# ProPrj.net
KiCad netlist of a schematic drawn in EasyEDA Pro
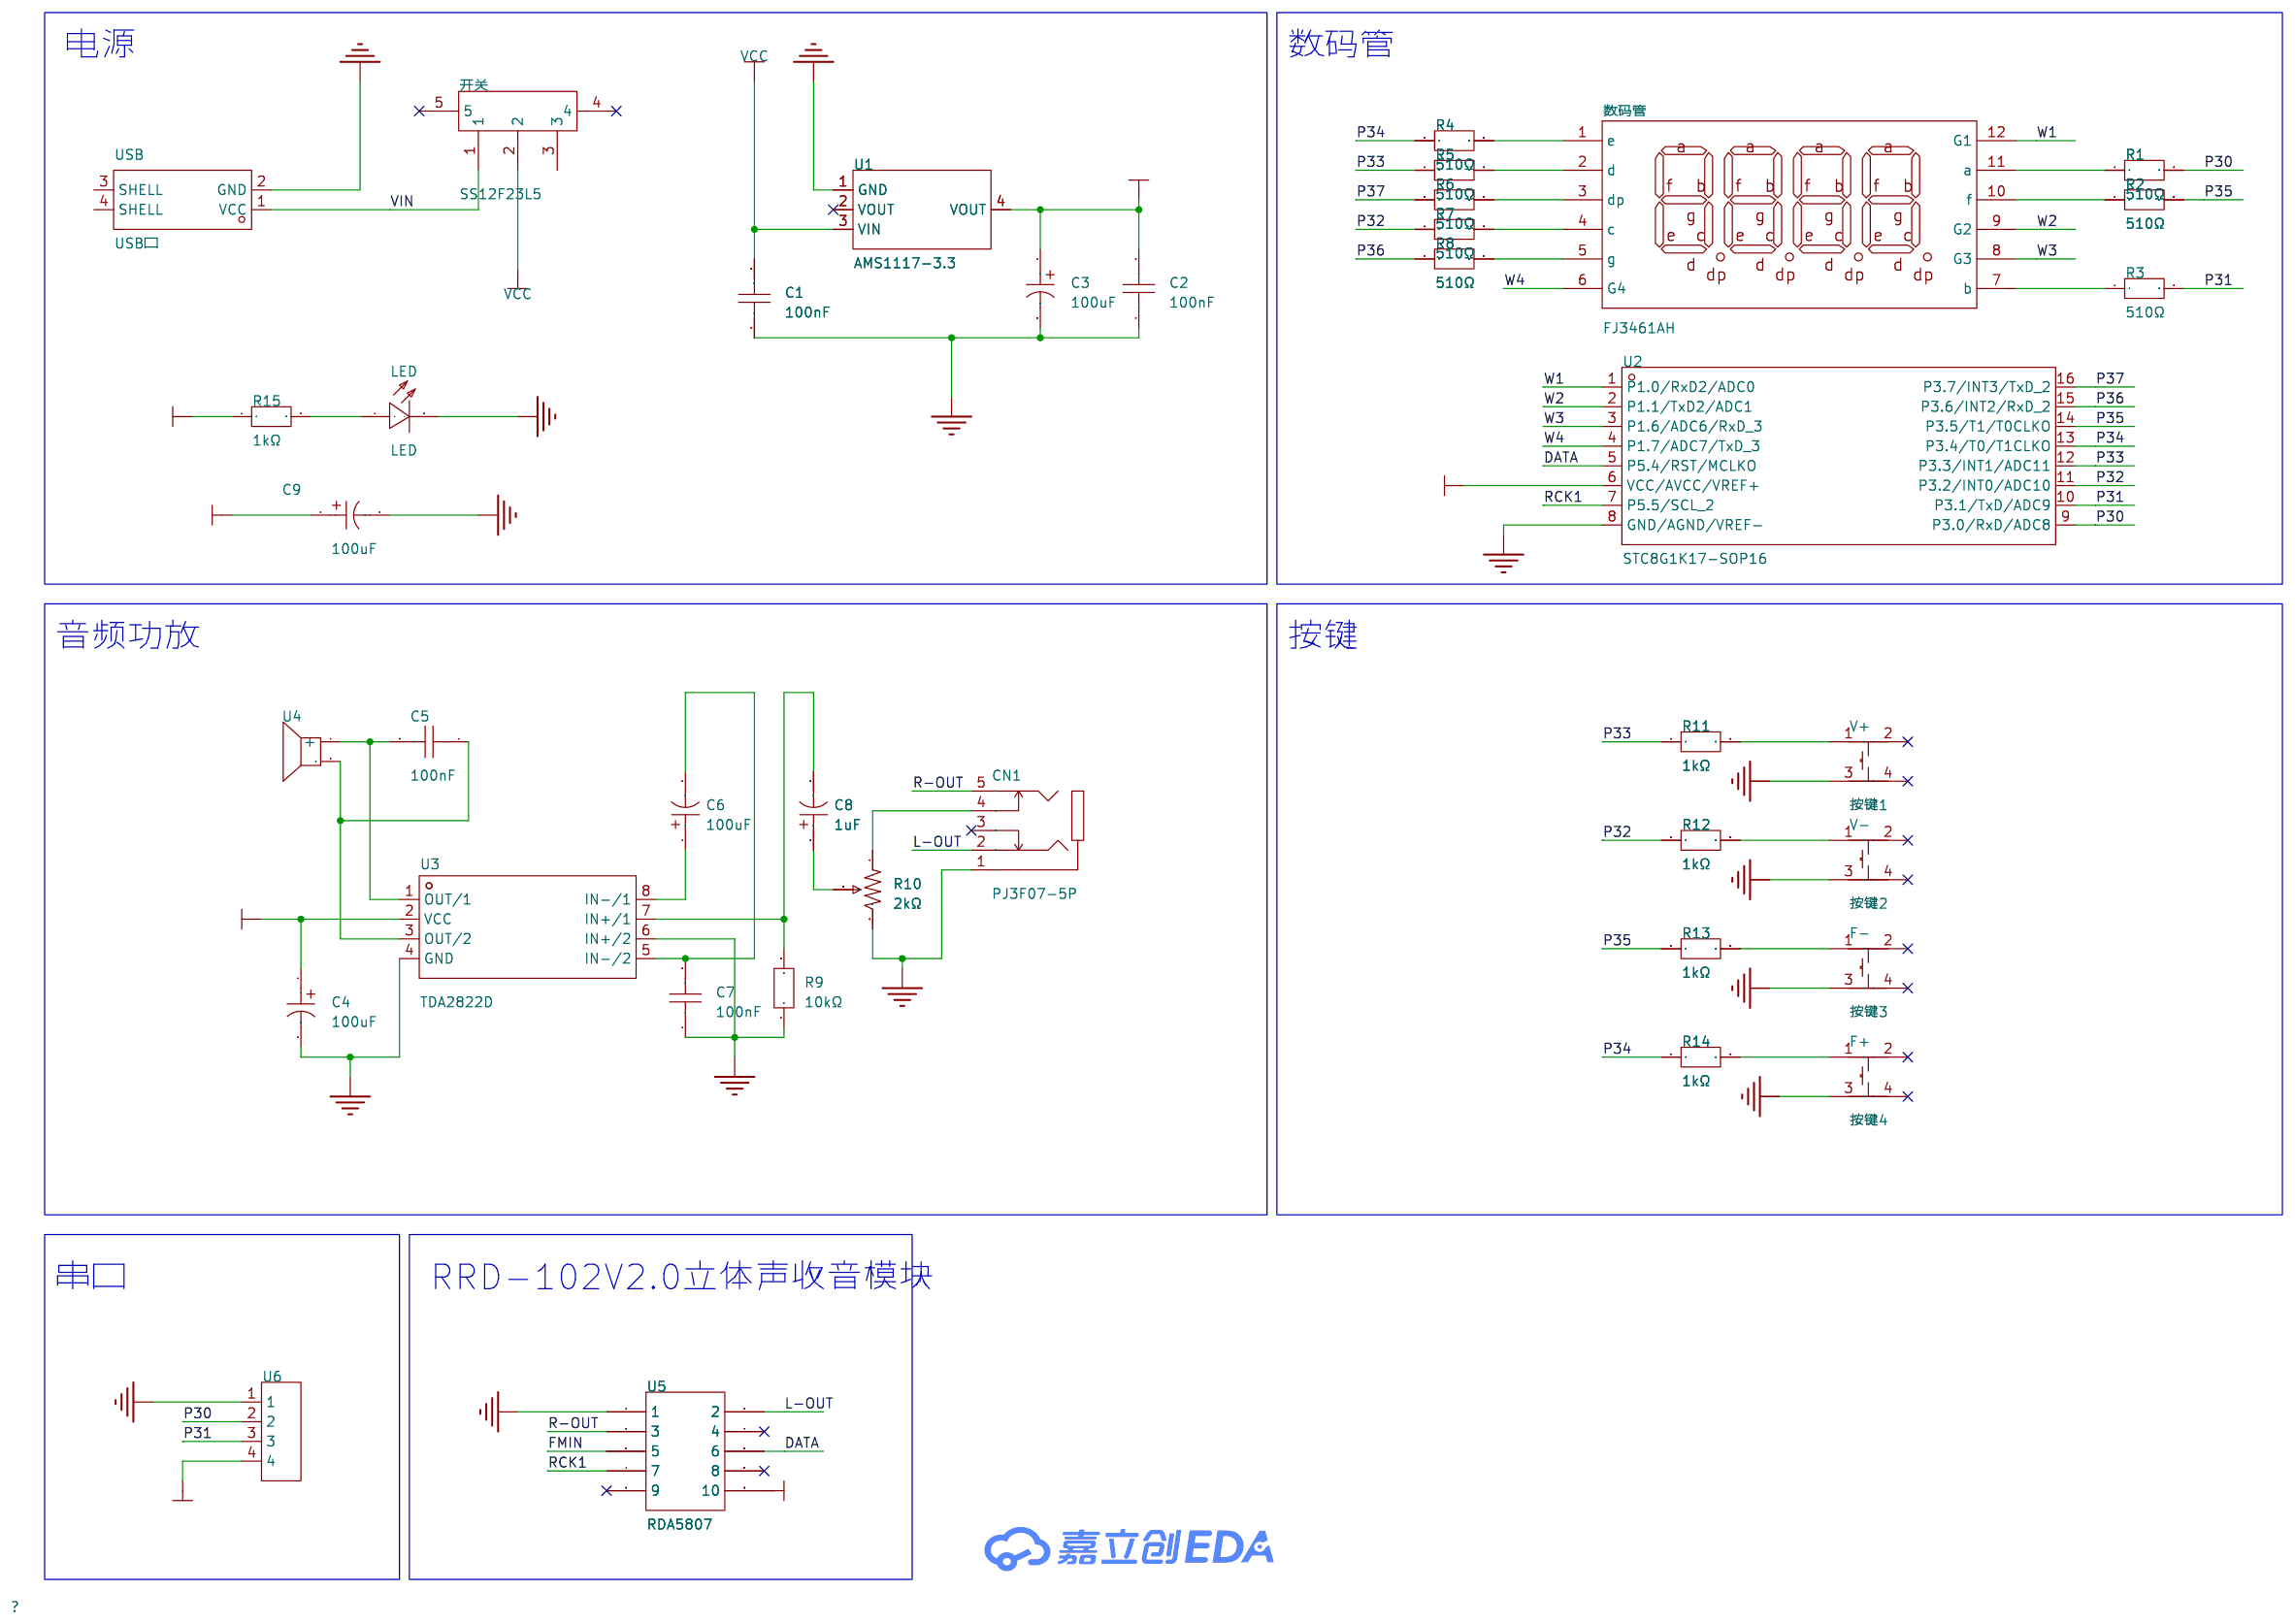
[diagram p0: P1]
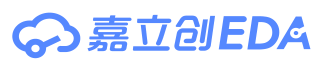
[diagram p1: P2]

(export (version "E")
  (design (tool "Eeschema 10.0.6"))
  (components
    (comp (ref "C1")
      (value "100nF")
      (footprint "easyedapro:C0603")
      (description "容值:100nF;精度:±10%;额定电压:50V;温度系数:X7R;")
      (fields
        (field (name "Manufacturer Part") "CC0603KRX7R9BB104")
        (field (name "Manufacturer") "YAGEO(国巨)")
      )
      (libsource (lib "easyedapro") (part "CC0603KRX7R9BB104"))
    )
    (comp (ref "C2")
      (value "100nF")
      (footprint "easyedapro:C0603")
      (description "容值:100nF;精度:±10%;额定电压:50V;温度系数:X7R;")
      (fields
        (field (name "Manufacturer Part") "CC0603KRX7R9BB104")
        (field (name "Manufacturer") "YAGEO(国巨)")
      )
      (libsource (lib "easyedapro") (part "CC0603KRX7R9BB104"))
    )
    (comp (ref "C3")
      (value "100uF")
      (footprint "easyedapro:CAP-TH_BD8.0-P3.50-D0.6-FD_1")
      (libsource (lib "easyedapro") (part "100UF_C9900016884"))
    )
    (comp (ref "C4")
      (value "100uF")
      (footprint "easyedapro:CAP-TH_BD8.0-P3.50-D0.6-FD_1")
      (libsource (lib "easyedapro") (part "100UF_C9900016884"))
    )
    (comp (ref "C5")
      (value "100nF")
      (footprint "easyedapro:C0603")
      (description "容值:100nF;精度:±10%;额定电压:50V;温度系数:X7R;")
      (fields
        (field (name "Manufacturer Part") "CC0603KRX7R9BB104")
        (field (name "Manufacturer") "YAGEO(国巨)")
      )
      (libsource (lib "easyedapro") (part "CC0603KRX7R9BB104"))
    )
    (comp (ref "C6")
      (value "100uF")
      (footprint "easyedapro:CAP-TH_BD8.0-P3.50-D0.6-FD_1")
      (libsource (lib "easyedapro") (part "100UF_C9900016884"))
    )
    (comp (ref "C7")
      (value "100nF")
      (footprint "easyedapro:C0603")
      (description "容值:100nF;精度:±10%;额定电压:50V;温度系数:X7R;")
      (fields
        (field (name "Manufacturer Part") "CC0603KRX7R9BB104")
        (field (name "Manufacturer") "YAGEO(国巨)")
      )
      (libsource (lib "easyedapro") (part "CC0603KRX7R9BB104"))
    )
    (comp (ref "C8")
      (value "1uF")
      (footprint "easyedapro:CAP-TH_BD8.0-P3.50-D0.6-FD_1")
      (fields (field (name "Manufacturer Part") "RST50V1M4X5") (field (name "Manufacturer") "JIERR(捷而瑞)"))
      (libsource (lib "easyedapro") (part "100UF_C9900016884"))
    )
    (comp (ref "C9")
      (value "100uF")
      (footprint "easyedapro:CAP-TH_BD8.0-P3.50-D0.6-FD_1")
      (libsource (lib "easyedapro") (part "100UF_C9900016884"))
    )
    (comp (ref "CN1")
      (value "PJ3F07-5P")
      (footprint "easyedapro:AUDIO-TH_PJ3F07-5P")
      (description "连接器类型:3.5mm耳机座;额定电流:500mA;额定电压:30V;触头材质:铜;触头镀层:银;工作温度:-30°C~+70°C;")
      (fields (field (name "Manufacturer") "SHOU HAN(首韩)"))
      (libsource (lib "easyedapro") (part "PJ3F07-5P"))
    )
    (comp (ref "F+")
      (value "按键4")
      (footprint "easyedapro:KEY-SMD_4P-L6.0-W6.0-P4.50-LS8.6")
      (fields (field (name "Manufacturer") "Megastar(兆星)"))
      (libsource (lib "easyedapro") (part "ZX-QC66-7.5TP"))
    )
    (comp (ref "F-")
      (value "按键3")
      (footprint "easyedapro:KEY-SMD_4P-L6.0-W6.0-P4.50-LS8.6")
      (fields (field (name "Manufacturer") "Megastar(兆星)"))
      (libsource (lib "easyedapro") (part "ZX-QC66-7.5TP"))
    )
    (comp (ref "LED")
      (value "LED")
      (footprint "easyedapro:LED-TH_BD4.0-P2.54-FD_RED")
      (libsource (lib "easyedapro") (part "LED_C9900015665"))
    )
    (comp (ref "R1")
      (value "510Ω")
      (footprint "easyedapro:R0402")
      (description "电阻类型:厚膜电阻;阻值:510Ω;精度:±1%;功率:62.5mW;工作电压:50V;温度系数:±100ppm/°C;")
      (fields
        (field (name "Manufacturer Part") "0805W8F5100T5E")
        (field (name "Manufacturer") "UNI-ROYAL(厚声)")
      )
      (libsource (lib "easyedapro") (part "FRC0402F5100TS"))
    )
    (comp (ref "R2")
      (value "510Ω")
      (footprint "easyedapro:R0402")
      (description "电阻类型:厚膜电阻;阻值:510Ω;精度:±1%;功率:62.5mW;工作电压:50V;温度系数:±100ppm/°C;")
      (fields
        (field (name "Manufacturer Part") "0805W8F5100T5E")
        (field (name "Manufacturer") "UNI-ROYAL(厚声)")
      )
      (libsource (lib "easyedapro") (part "FRC0402F5100TS"))
    )
    (comp (ref "R3")
      (value "510Ω")
      (footprint "easyedapro:R0402")
      (description "电阻类型:厚膜电阻;阻值:510Ω;精度:±1%;功率:62.5mW;工作电压:50V;温度系数:±100ppm/°C;")
      (fields
        (field (name "Manufacturer Part") "0805W8F5100T5E")
        (field (name "Manufacturer") "UNI-ROYAL(厚声)")
      )
      (libsource (lib "easyedapro") (part "FRC0402F5100TS"))
    )
    (comp (ref "R4")
      (value "510Ω")
      (footprint "easyedapro:R0402")
      (description "电阻类型:厚膜电阻;阻值:510Ω;精度:±1%;功率:62.5mW;工作电压:50V;温度系数:±100ppm/°C;")
      (fields
        (field (name "Manufacturer Part") "0805W8F5100T5E")
        (field (name "Manufacturer") "UNI-ROYAL(厚声)")
      )
      (libsource (lib "easyedapro") (part "FRC0402F5100TS"))
    )
    (comp (ref "R5")
      (value "510Ω")
      (footprint "easyedapro:R0402")
      (description "电阻类型:厚膜电阻;阻值:510Ω;精度:±1%;功率:62.5mW;工作电压:50V;温度系数:±100ppm/°C;")
      (fields
        (field (name "Manufacturer Part") "0805W8F5100T5E")
        (field (name "Manufacturer") "UNI-ROYAL(厚声)")
      )
      (libsource (lib "easyedapro") (part "FRC0402F5100TS"))
    )
    (comp (ref "R6")
      (value "510Ω")
      (footprint "easyedapro:R0402")
      (description "电阻类型:厚膜电阻;阻值:510Ω;精度:±1%;功率:62.5mW;工作电压:50V;温度系数:±100ppm/°C;")
      (fields
        (field (name "Manufacturer Part") "0805W8F5100T5E")
        (field (name "Manufacturer") "UNI-ROYAL(厚声)")
      )
      (libsource (lib "easyedapro") (part "FRC0402F5100TS"))
    )
    (comp (ref "R7")
      (value "510Ω")
      (footprint "easyedapro:R0402")
      (description "电阻类型:厚膜电阻;阻值:510Ω;精度:±1%;功率:62.5mW;工作电压:50V;温度系数:±100ppm/°C;")
      (fields
        (field (name "Manufacturer Part") "0805W8F5100T5E")
        (field (name "Manufacturer") "UNI-ROYAL(厚声)")
      )
      (libsource (lib "easyedapro") (part "FRC0402F5100TS"))
    )
    (comp (ref "R8")
      (value "510Ω")
      (footprint "easyedapro:R0402")
      (description "电阻类型:厚膜电阻;阻值:510Ω;精度:±1%;功率:62.5mW;工作电压:50V;温度系数:±100ppm/°C;")
      (fields
        (field (name "Manufacturer Part") "0805W8F5100T5E")
        (field (name "Manufacturer") "UNI-ROYAL(厚声)")
      )
      (libsource (lib "easyedapro") (part "FRC0402F5100TS"))
    )
    (comp (ref "R9")
      (value "10kΩ")
      (footprint "easyedapro:R0603")
      (description "电阻类型:厚膜电阻;阻值:10kΩ;精度:±5%;功率:100mW;工作电压:75V;温度系数:±100ppm/°C;")
      (fields
        (field (name "Manufacturer Part") "0805W8F1002T5E")
        (field (name "Manufacturer") "UNI-ROYAL(厚声)")
      )
      (libsource (lib "easyedapro") (part "FRR0603J103 TS"))
    )
    (comp (ref "R10")
      (value "2kΩ")
      (footprint "easyedapro:RES-ADJ-TH_3362X")
      (description "阻值:2kΩ;精度:±10%;功率:500mW;温度系数:±250ppm/°C;")
      (fields (field (name "Manufacturer Part") "3362X-1-202") (field (name "Manufacturer") "JIERR(捷而瑞)"))
      (libsource (lib "easyedapro") (part "3362X-1-202"))
    )
    (comp (ref "R11")
      (value "1kΩ")
      (footprint "easyedapro:R0603")
      (description "电阻类型:厚膜电阻;阻值:1kΩ;精度:±5%;功率:100mW;工作电压:150V;温度系数:±100ppm/°C;")
      (fields (field (name "Manufacturer Part") "SR0603JR-071KL") (field (name "Manufacturer") "YAGEO(国巨)"))
      (libsource (lib "easyedapro") (part "SR0603JR-071KL"))
    )
    (comp (ref "R12")
      (value "1kΩ")
      (footprint "easyedapro:R0603")
      (description "电阻类型:厚膜电阻;阻值:1kΩ;精度:±5%;功率:100mW;工作电压:150V;温度系数:±100ppm/°C;")
      (fields (field (name "Manufacturer Part") "SR0603JR-071KL") (field (name "Manufacturer") "YAGEO(国巨)"))
      (libsource (lib "easyedapro") (part "SR0603JR-071KL"))
    )
    (comp (ref "R13")
      (value "1kΩ")
      (footprint "easyedapro:R0603")
      (description "电阻类型:厚膜电阻;阻值:1kΩ;精度:±5%;功率:100mW;工作电压:150V;温度系数:±100ppm/°C;")
      (fields (field (name "Manufacturer Part") "SR0603JR-071KL") (field (name "Manufacturer") "YAGEO(国巨)"))
      (libsource (lib "easyedapro") (part "SR0603JR-071KL"))
    )
    (comp (ref "R14")
      (value "1kΩ")
      (footprint "easyedapro:R0603")
      (description "电阻类型:厚膜电阻;阻值:1kΩ;精度:±5%;功率:100mW;工作电压:150V;温度系数:±100ppm/°C;")
      (fields (field (name "Manufacturer Part") "SR0603JR-071KL") (field (name "Manufacturer") "YAGEO(国巨)"))
      (libsource (lib "easyedapro") (part "SR0603JR-071KL"))
    )
    (comp (ref "R15")
      (value "1kΩ")
      (footprint "easyedapro:R0603")
      (description "电阻类型:厚膜电阻;阻值:1kΩ;精度:±5%;功率:100mW;工作电压:150V;温度系数:±100ppm/°C;")
      (fields
        (field (name "Manufacturer Part") "0805W8F1001T5E")
        (field (name "Manufacturer") "UNI-ROYAL(厚声)")
      )
      (libsource (lib "easyedapro") (part "SR0603JR-071KL"))
    )
    (comp (ref "U1")
      (value "AMS1117-3.3")
      (footprint "easyedapro:SOT-223-3_L6.5-W3.4-P2.30-LS7.0-BR")
      (description "输出类型:固定;工作电压:16V;输出电压:3.3V;输出电流:1A;电源纹波抑制比(PSRR):72dB@(120Hz);输出极性:正极;")
      (fields (field (name "Manufacturer") "AMS"))
      (libsource (lib "easyedapro") (part "AMS1117-3.3"))
    )
    (comp (ref "U2")
      (value "STC8G1K17-SOP16")
      (footprint "easyedapro:SOP-16_L9.9-W3.9-P1.27-LS6.0-BL")
      (libsource (lib "easyedapro") (part "STC8G1K17-SOP16"))
    )
    (comp (ref "U3")
      (value "TDA2822D")
      (footprint "easyedapro:SOIC-8_L4.9-W3.9-P1.27-LS6.0-BL")
      (description "功放类型:AB类功放;扬声器通道数:单声道;输出功率:380mWx2@8Ω；1Wx1@32Ω;")
      (fields (field (name "Manufacturer") "ST(意法半导体)"))
      (libsource (lib "easyedapro") (part "TDA2822D"))
    )
    (comp (ref "U4")
      (value "2.048kHz")
      (footprint "easyedapro:BUZ-TH_BD16.0-P7.60-D0.7")
      (description "驱动方式:无源(外部驱动);构造类型:电磁式;额定电压:12V;频率:2.048kHz;声压(SPL):85dB;")
      (fields (field (name "Manufacturer Part") "AP-1612Z-P") (field (name "Manufacturer") "Dragonstate(华龙)"))
      (libsource (lib "easyedapro") (part "AP-1612Z-P"))
    )
    (comp (ref "U5")
      (value "Header-D-F 2x5P")
      (footprint "easyedapro:RDA5807")
      (description "2x5pin, 直插, 双排座")
      (libsource (lib "easyedapro") (part "Header-D-F 2x5P"))
    )
    (comp (ref "U6")
      (value "HX PZ2.54-1x4P ZZ")
      (footprint "easyedapro:HDR-TH_4P-P2.54-V-M")
      (fields (field (name "Manufacturer") "hanxia(韩下)"))
      (libsource (lib "easyedapro") (part "HX PZ2.54-1X4P ZZ"))
    )
    (comp (ref "USB")
      (value "USB口")
      (footprint "easyedapro:MICRO-USB-TH_KH-MICRO-DIP-2P")
      (description "连接器类型:Micro-B;协议标准:USB 2.0;公母:母;安装方式:弯插;触点数量:5P;端口数量:1;额定电流 - 电源:1.5A;工作温度:-;")
      (fields (field (name "Manufacturer") "kinghelm(金航标)"))
      (libsource (lib "easyedapro") (part "KH-MICRO-DIP-2P"))
    )
    (comp (ref "V+")
      (value "按键1")
      (footprint "easyedapro:KEY-SMD_4P-L6.0-W6.0-P4.50-LS8.6")
      (fields (field (name "Manufacturer") "Megastar(兆星)"))
      (libsource (lib "easyedapro") (part "ZX-QC66-7.5TP"))
    )
    (comp (ref "V-")
      (value "按键2")
      (footprint "easyedapro:KEY-SMD_4P-L6.0-W6.0-P4.50-LS8.6")
      (fields (field (name "Manufacturer") "Megastar(兆星)"))
      (libsource (lib "easyedapro") (part "ZX-QC66-7.5TP"))
    )
    (comp (ref "开关")
      (value "SS12F23L5")
      (footprint "easyedapro:SW-TH_XKBCONNECTIVITY_SS12F23L5")
      (description "电路结构:单刀双掷;安装方式:-;开关颜色:黑色;额定电流:300mA;额定电压:50V;工作寿命:1万次;")
      (fields (field (name "Manufacturer") "XKB Connection(中国星坤)"))
      (libsource (lib "easyedapro") (part "SS12F23L5"))
    )
    (comp (ref "数码管")
      (value "FJ3461AH")
      (footprint "easyedapro:LED-SEG-TH_12P-L30.0-W14.0-P2.54-S10.16-BL")
      (description "数码管位数:4位;字符尺寸(英寸):0.36;耗散功率(Pd):-;发光颜色:红色;LED极性:共阴极;")
      (fields (field (name "Manufacturer") "志浩"))
      (libsource (lib "easyedapro") (part "FJ3461AH"))
    )
  )
  (nets
    (net (code "1") (name "3.3V") (class "Default")
      (node (ref "C2") (pin "2") (pinfunction "2_2") (pintype "unspecified"))
      (node (ref "C3") (pin "1") (pinfunction "1_1") (pintype "input"))
      (node (ref "C4") (pin "1") (pinfunction "1_1") (pintype "input"))
      (node (ref "C9") (pin "1") (pinfunction "1_1") (pintype "input"))
      (node (ref "R15") (pin "1") (pinfunction "1_1") (pintype "unspecified"))
      (node (ref "U1") (pin "4") (pinfunction "VOUT_4") (pintype "unspecified"))
      (node (ref "U2") (pin "6") (pinfunction "VCC/AVCC/VREF+_6") (pintype "unspecified"))
      (node (ref "U3") (pin "2") (pinfunction "VCC_2") (pintype "unspecified"))
      (node (ref "U5") (pin "10") (pinfunction "10_10") (pintype "unspecified"))
      (node (ref "U6") (pin "4") (pinfunction "4_4") (pintype "unspecified"))
    )
    (net (code "2") (name "DATA") (class "Default")
      (node (ref "U2") (pin "5") (pinfunction "P5.4/RST/MCLKO_5") (pintype "unspecified"))
      (node (ref "U5") (pin "6") (pinfunction "6_6") (pintype "unspecified"))
    )
    (net (code "3") (name "FMIN") (class "Default")
      (node (ref "U5") (pin "5") (pinfunction "5_5") (pintype "unspecified"))
    )
    (net (code "4") (name "GND") (class "Default")
      (node (ref "C1") (pin "1") (pinfunction "1_1") (pintype "unspecified"))
      (node (ref "C2") (pin "1") (pinfunction "1_1") (pintype "unspecified"))
      (node (ref "C3") (pin "2") (pinfunction "2_2") (pintype "input"))
      (node (ref "C4") (pin "2") (pinfunction "2_2") (pintype "input"))
      (node (ref "C7") (pin "1") (pinfunction "1_1") (pintype "unspecified"))
      (node (ref "C9") (pin "2") (pinfunction "2_2") (pintype "input"))
      (node (ref "CN1") (pin "1") (pinfunction "A_1") (pintype "input"))
      (node (ref "F+") (pin "3") (pinfunction "3_3") (pintype "unspecified"))
      (node (ref "F-") (pin "3") (pinfunction "3_3") (pintype "unspecified"))
      (node (ref "LED") (pin "2") (pinfunction "-_2") (pintype "unspecified"))
      (node (ref "R10") (pin "3") (pinfunction "3_3") (pintype "unspecified"))
      (node (ref "R9") (pin "1") (pinfunction "1_1") (pintype "unspecified"))
      (node (ref "U1") (pin "1") (pinfunction "GND_1") (pintype "unspecified"))
      (node (ref "U2") (pin "8") (pinfunction "GND/AGND/VREF-_8") (pintype "unspecified"))
      (node (ref "U3") (pin "4") (pinfunction "GND_4") (pintype "unspecified"))
      (node (ref "U3") (pin "6") (pinfunction "IN+/2_6") (pintype "unspecified"))
      (node (ref "U5") (pin "1") (pinfunction "1_1") (pintype "unspecified"))
      (node (ref "U6") (pin "1") (pinfunction "1_1") (pintype "unspecified"))
      (node (ref "USB") (pin "2") (pinfunction "GND_2") (pintype "unspecified"))
      (node (ref "V+") (pin "3") (pinfunction "3_3") (pintype "unspecified"))
      (node (ref "V-") (pin "3") (pinfunction "3_3") (pintype "unspecified"))
    )
    (net (code "5") (name "L-OUT") (class "Default")
      (node (ref "CN1") (pin "2") (pinfunction "B_2") (pintype "input"))
      (node (ref "U5") (pin "2") (pinfunction "2_2") (pintype "unspecified"))
    )
    (net (code "6") (name "Net-(C8-Pad1)") (class "Default")
      (node (ref "C8") (pin "1") (pinfunction "1_1") (pintype "input"))
      (node (ref "R10") (pin "2") (pinfunction "2_2") (pintype "unspecified"))
    )
    (net (code "7") (name "Net-(CN1-D)") (class "Default")
      (node (ref "CN1") (pin "4") (pinfunction "D_4") (pintype "input"))
      (node (ref "R10") (pin "1") (pinfunction "1_1") (pintype "unspecified"))
    )
    (net (code "8") (name "Net-(F+-Pad1)") (class "Default")
      (node (ref "F+") (pin "1") (pinfunction "1_1") (pintype "unspecified"))
      (node (ref "R14") (pin "2") (pinfunction "2_2") (pintype "unspecified"))
    )
    (net (code "9") (name "Net-(F--Pad1)") (class "Default")
      (node (ref "F-") (pin "1") (pinfunction "1_1") (pintype "unspecified"))
      (node (ref "R13") (pin "2") (pinfunction "2_2") (pintype "unspecified"))
    )
    (net (code "10") (name "Net-(LED-+)") (class "Default")
      (node (ref "LED") (pin "1") (pinfunction "+_1") (pintype "unspecified"))
      (node (ref "R15") (pin "2") (pinfunction "2_2") (pintype "unspecified"))
    )
    (net (code "11") (name "Net-(R11-Pad2)") (class "Default")
      (node (ref "R11") (pin "2") (pinfunction "2_2") (pintype "unspecified"))
      (node (ref "V+") (pin "1") (pinfunction "1_1") (pintype "unspecified"))
    )
    (net (code "12") (name "Net-(R12-Pad2)") (class "Default")
      (node (ref "R12") (pin "2") (pinfunction "2_2") (pintype "unspecified"))
      (node (ref "V-") (pin "1") (pinfunction "1_1") (pintype "unspecified"))
    )
    (net (code "13") (name "Net-(U3-IN+{slash}1)") (class "Default")
      (node (ref "C8") (pin "2") (pinfunction "2_2") (pintype "input"))
      (node (ref "R9") (pin "2") (pinfunction "2_2") (pintype "unspecified"))
      (node (ref "U3") (pin "7") (pinfunction "IN+/1_7") (pintype "unspecified"))
    )
    (net (code "14") (name "Net-(U3-IN-{slash}1)") (class "Default")
      (node (ref "C6") (pin "1") (pinfunction "1_1") (pintype "input"))
      (node (ref "U3") (pin "8") (pinfunction "IN-/1_8") (pintype "unspecified"))
    )
    (net (code "15") (name "Net-(U3-IN-{slash}2)") (class "Default")
      (node (ref "C6") (pin "2") (pinfunction "2_2") (pintype "input"))
      (node (ref "C7") (pin "2") (pinfunction "2_2") (pintype "unspecified"))
      (node (ref "U3") (pin "5") (pinfunction "IN-/2_5") (pintype "unspecified"))
    )
    (net (code "16") (name "Net-(U3-OUT{slash}1)") (class "Default")
      (node (ref "C5") (pin "2") (pinfunction "2_2") (pintype "unspecified"))
      (node (ref "U3") (pin "1") (pinfunction "OUT/1_1") (pintype "unspecified"))
      (node (ref "U4") (pin "1") (pinfunction "+_1") (pintype "unspecified"))
    )
    (net (code "17") (name "Net-(U3-OUT{slash}2)") (class "Default")
      (node (ref "C5") (pin "1") (pinfunction "1_1") (pintype "unspecified"))
      (node (ref "U3") (pin "3") (pinfunction "OUT/2_3") (pintype "unspecified"))
      (node (ref "U4") (pin "2") (pinfunction "2_2") (pintype "unspecified"))
    )
    (net (code "18") (name "Net-(数码管-a)") (class "Default")
      (node (ref "R1") (pin "1") (pinfunction "1_1") (pintype "unspecified"))
      (node (ref "数码管") (pin "11") (pinfunction "a_11") (pintype "input"))
    )
    (net (code "19") (name "Net-(数码管-b)") (class "Default")
      (node (ref "R3") (pin "1") (pinfunction "1_1") (pintype "unspecified"))
      (node (ref "数码管") (pin "7") (pinfunction "b_7") (pintype "input"))
    )
    (net (code "20") (name "Net-(数码管-c)") (class "Default")
      (node (ref "R7") (pin "2") (pinfunction "2_2") (pintype "unspecified"))
      (node (ref "数码管") (pin "4") (pinfunction "c_4") (pintype "input"))
    )
    (net (code "21") (name "Net-(数码管-d)") (class "Default")
      (node (ref "R5") (pin "2") (pinfunction "2_2") (pintype "unspecified"))
      (node (ref "数码管") (pin "2") (pinfunction "d_2") (pintype "input"))
    )
    (net (code "22") (name "Net-(数码管-dp)") (class "Default")
      (node (ref "R6") (pin "2") (pinfunction "2_2") (pintype "unspecified"))
      (node (ref "数码管") (pin "3") (pinfunction "dp_3") (pintype "input"))
    )
    (net (code "23") (name "Net-(数码管-e)") (class "Default")
      (node (ref "R4") (pin "2") (pinfunction "2_2") (pintype "unspecified"))
      (node (ref "数码管") (pin "1") (pinfunction "e_1") (pintype "input"))
    )
    (net (code "24") (name "Net-(数码管-f)") (class "Default")
      (node (ref "R2") (pin "1") (pinfunction "1_1") (pintype "unspecified"))
      (node (ref "数码管") (pin "10") (pinfunction "f_10") (pintype "input"))
    )
    (net (code "25") (name "Net-(数码管-g)") (class "Default")
      (node (ref "R8") (pin "2") (pinfunction "2_2") (pintype "unspecified"))
      (node (ref "数码管") (pin "5") (pinfunction "g_5") (pintype "input"))
    )
    (net (code "26") (name "P30") (class "Default")
      (node (ref "R1") (pin "2") (pinfunction "2_2") (pintype "unspecified"))
      (node (ref "U2") (pin "9") (pinfunction "P3.0/RxD/ADC8_9") (pintype "unspecified"))
      (node (ref "U6") (pin "2") (pinfunction "2_2") (pintype "unspecified"))
    )
    (net (code "27") (name "P31") (class "Default")
      (node (ref "R3") (pin "2") (pinfunction "2_2") (pintype "unspecified"))
      (node (ref "U2") (pin "10") (pinfunction "P3.1/TxD/ADC9_10") (pintype "unspecified"))
      (node (ref "U6") (pin "3") (pinfunction "3_3") (pintype "unspecified"))
    )
    (net (code "28") (name "P32") (class "Default")
      (node (ref "R12") (pin "1") (pinfunction "1_1") (pintype "unspecified"))
      (node (ref "R7") (pin "1") (pinfunction "1_1") (pintype "unspecified"))
      (node (ref "U2") (pin "11") (pinfunction "P3.2/INT0/ADC10_11") (pintype "unspecified"))
    )
    (net (code "29") (name "P33") (class "Default")
      (node (ref "R11") (pin "1") (pinfunction "1_1") (pintype "unspecified"))
      (node (ref "R5") (pin "1") (pinfunction "1_1") (pintype "unspecified"))
      (node (ref "U2") (pin "12") (pinfunction "P3.3/INT1/ADC11_12") (pintype "unspecified"))
    )
    (net (code "30") (name "P34") (class "Default")
      (node (ref "R14") (pin "1") (pinfunction "1_1") (pintype "unspecified"))
      (node (ref "R4") (pin "1") (pinfunction "1_1") (pintype "unspecified"))
      (node (ref "U2") (pin "13") (pinfunction "P3.4/T0/T1CLKO_13") (pintype "unspecified"))
    )
    (net (code "31") (name "P35") (class "Default")
      (node (ref "R13") (pin "1") (pinfunction "1_1") (pintype "unspecified"))
      (node (ref "R2") (pin "2") (pinfunction "2_2") (pintype "unspecified"))
      (node (ref "U2") (pin "14") (pinfunction "P3.5/T1/T0CLKO_14") (pintype "unspecified"))
    )
    (net (code "32") (name "P36") (class "Default")
      (node (ref "R8") (pin "1") (pinfunction "1_1") (pintype "unspecified"))
      (node (ref "U2") (pin "15") (pinfunction "P3.6/INT2/RxD_2_15") (pintype "unspecified"))
    )
    (net (code "33") (name "P37") (class "Default")
      (node (ref "R6") (pin "1") (pinfunction "1_1") (pintype "unspecified"))
      (node (ref "U2") (pin "16") (pinfunction "P3.7/INT3/TxD_2_16") (pintype "unspecified"))
    )
    (net (code "34") (name "R-OUT") (class "Default")
      (node (ref "CN1") (pin "5") (pinfunction "E_5") (pintype "input"))
      (node (ref "U5") (pin "3") (pinfunction "3_3") (pintype "unspecified"))
    )
    (net (code "35") (name "RCK1") (class "Default")
      (node (ref "U2") (pin "7") (pinfunction "P5.5/SCL_2_7") (pintype "unspecified"))
      (node (ref "U5") (pin "7") (pinfunction "7_7") (pintype "unspecified"))
    )
    (net (code "36") (name "VCC") (class "Default")
      (node (ref "C1") (pin "2") (pinfunction "2_2") (pintype "unspecified"))
      (node (ref "U1") (pin "3") (pinfunction "VIN_3") (pintype "unspecified"))
      (node (ref "开关") (pin "2") (pinfunction "2_2") (pintype "unspecified"))
    )
    (net (code "37") (name "VIN") (class "Default")
      (node (ref "USB") (pin "1") (pinfunction "VCC_1") (pintype "unspecified"))
      (node (ref "开关") (pin "1") (pinfunction "1_1") (pintype "unspecified"))
    )
    (net (code "38") (name "W1") (class "Default")
      (node (ref "U2") (pin "1") (pinfunction "P1.0/RxD2/ADC0_1") (pintype "unspecified"))
      (node (ref "数码管") (pin "12") (pinfunction "G1_12") (pintype "input"))
    )
    (net (code "39") (name "W2") (class "Default")
      (node (ref "U2") (pin "2") (pinfunction "P1.1/TxD2/ADC1_2") (pintype "unspecified"))
      (node (ref "数码管") (pin "9") (pinfunction "G2_9") (pintype "input"))
    )
    (net (code "40") (name "W3") (class "Default")
      (node (ref "U2") (pin "3") (pinfunction "P1.6/ADC6/RxD_3_3") (pintype "unspecified"))
      (node (ref "数码管") (pin "8") (pinfunction "G3_8") (pintype "input"))
    )
    (net (code "41") (name "W4") (class "Default")
      (node (ref "U2") (pin "4") (pinfunction "P1.7/ADC7/TxD_3_4") (pintype "unspecified"))
      (node (ref "数码管") (pin "6") (pinfunction "G4_6") (pintype "input"))
    )
    (net (code "42") (name "unconnected-(CN1-C-Pad3)") (class "Default")
      (node (ref "CN1") (pin "3") (pinfunction "C_3") (pintype "input+no_connect"))
    )
    (net (code "43") (name "unconnected-(F+-Pad2)") (class "Default")
      (node (ref "F+") (pin "2") (pinfunction "2_2") (pintype "unspecified+no_connect"))
    )
    (net (code "44") (name "unconnected-(F+-Pad4)") (class "Default")
      (node (ref "F+") (pin "4") (pinfunction "4_4") (pintype "unspecified+no_connect"))
    )
    (net (code "45") (name "unconnected-(F--Pad2)") (class "Default")
      (node (ref "F-") (pin "2") (pinfunction "2_2") (pintype "unspecified+no_connect"))
    )
    (net (code "46") (name "unconnected-(F--Pad4)") (class "Default")
      (node (ref "F-") (pin "4") (pinfunction "4_4") (pintype "unspecified+no_connect"))
    )
    (net (code "47") (name "unconnected-(U1-VOUT-Pad2)") (class "Default")
      (node (ref "U1") (pin "2") (pinfunction "VOUT_2") (pintype "unspecified+no_connect"))
    )
    (net (code "48") (name "unconnected-(U5-Pad4)") (class "Default")
      (node (ref "U5") (pin "4") (pinfunction "4_4") (pintype "unspecified+no_connect"))
    )
    (net (code "49") (name "unconnected-(U5-Pad8)") (class "Default")
      (node (ref "U5") (pin "8") (pinfunction "8_8") (pintype "unspecified+no_connect"))
    )
    (net (code "50") (name "unconnected-(U5-Pad9)") (class "Default")
      (node (ref "U5") (pin "9") (pinfunction "9_9") (pintype "unspecified+no_connect"))
    )
    (net (code "51") (name "unconnected-(USB-SHELL-Pad3)") (class "Default")
      (node (ref "USB") (pin "3") (pinfunction "SHELL_3") (pintype "unspecified"))
    )
    (net (code "52") (name "unconnected-(USB-SHELL-Pad4)") (class "Default")
      (node (ref "USB") (pin "4") (pinfunction "SHELL_4") (pintype "unspecified"))
    )
    (net (code "53") (name "unconnected-(V+-Pad2)") (class "Default")
      (node (ref "V+") (pin "2") (pinfunction "2_2") (pintype "unspecified+no_connect"))
    )
    (net (code "54") (name "unconnected-(V+-Pad4)") (class "Default")
      (node (ref "V+") (pin "4") (pinfunction "4_4") (pintype "unspecified+no_connect"))
    )
    (net (code "55") (name "unconnected-(V--Pad2)") (class "Default")
      (node (ref "V-") (pin "2") (pinfunction "2_2") (pintype "unspecified+no_connect"))
    )
    (net (code "56") (name "unconnected-(V--Pad4)") (class "Default")
      (node (ref "V-") (pin "4") (pinfunction "4_4") (pintype "unspecified+no_connect"))
    )
    (net (code "57") (name "unconnected-(开关-Pad3)") (class "Default")
      (node (ref "开关") (pin "3") (pinfunction "3_3") (pintype "unspecified"))
    )
    (net (code "58") (name "unconnected-(开关-Pad4)") (class "Default")
      (node (ref "开关") (pin "4") (pinfunction "4_4") (pintype "unspecified+no_connect"))
    )
    (net (code "59") (name "unconnected-(开关-Pad5)") (class "Default")
      (node (ref "开关") (pin "5") (pinfunction "5_5") (pintype "unspecified+no_connect"))
    )
  )
)
